# untitled.net
KiCad netlist of a schematic drawn in EAGLE
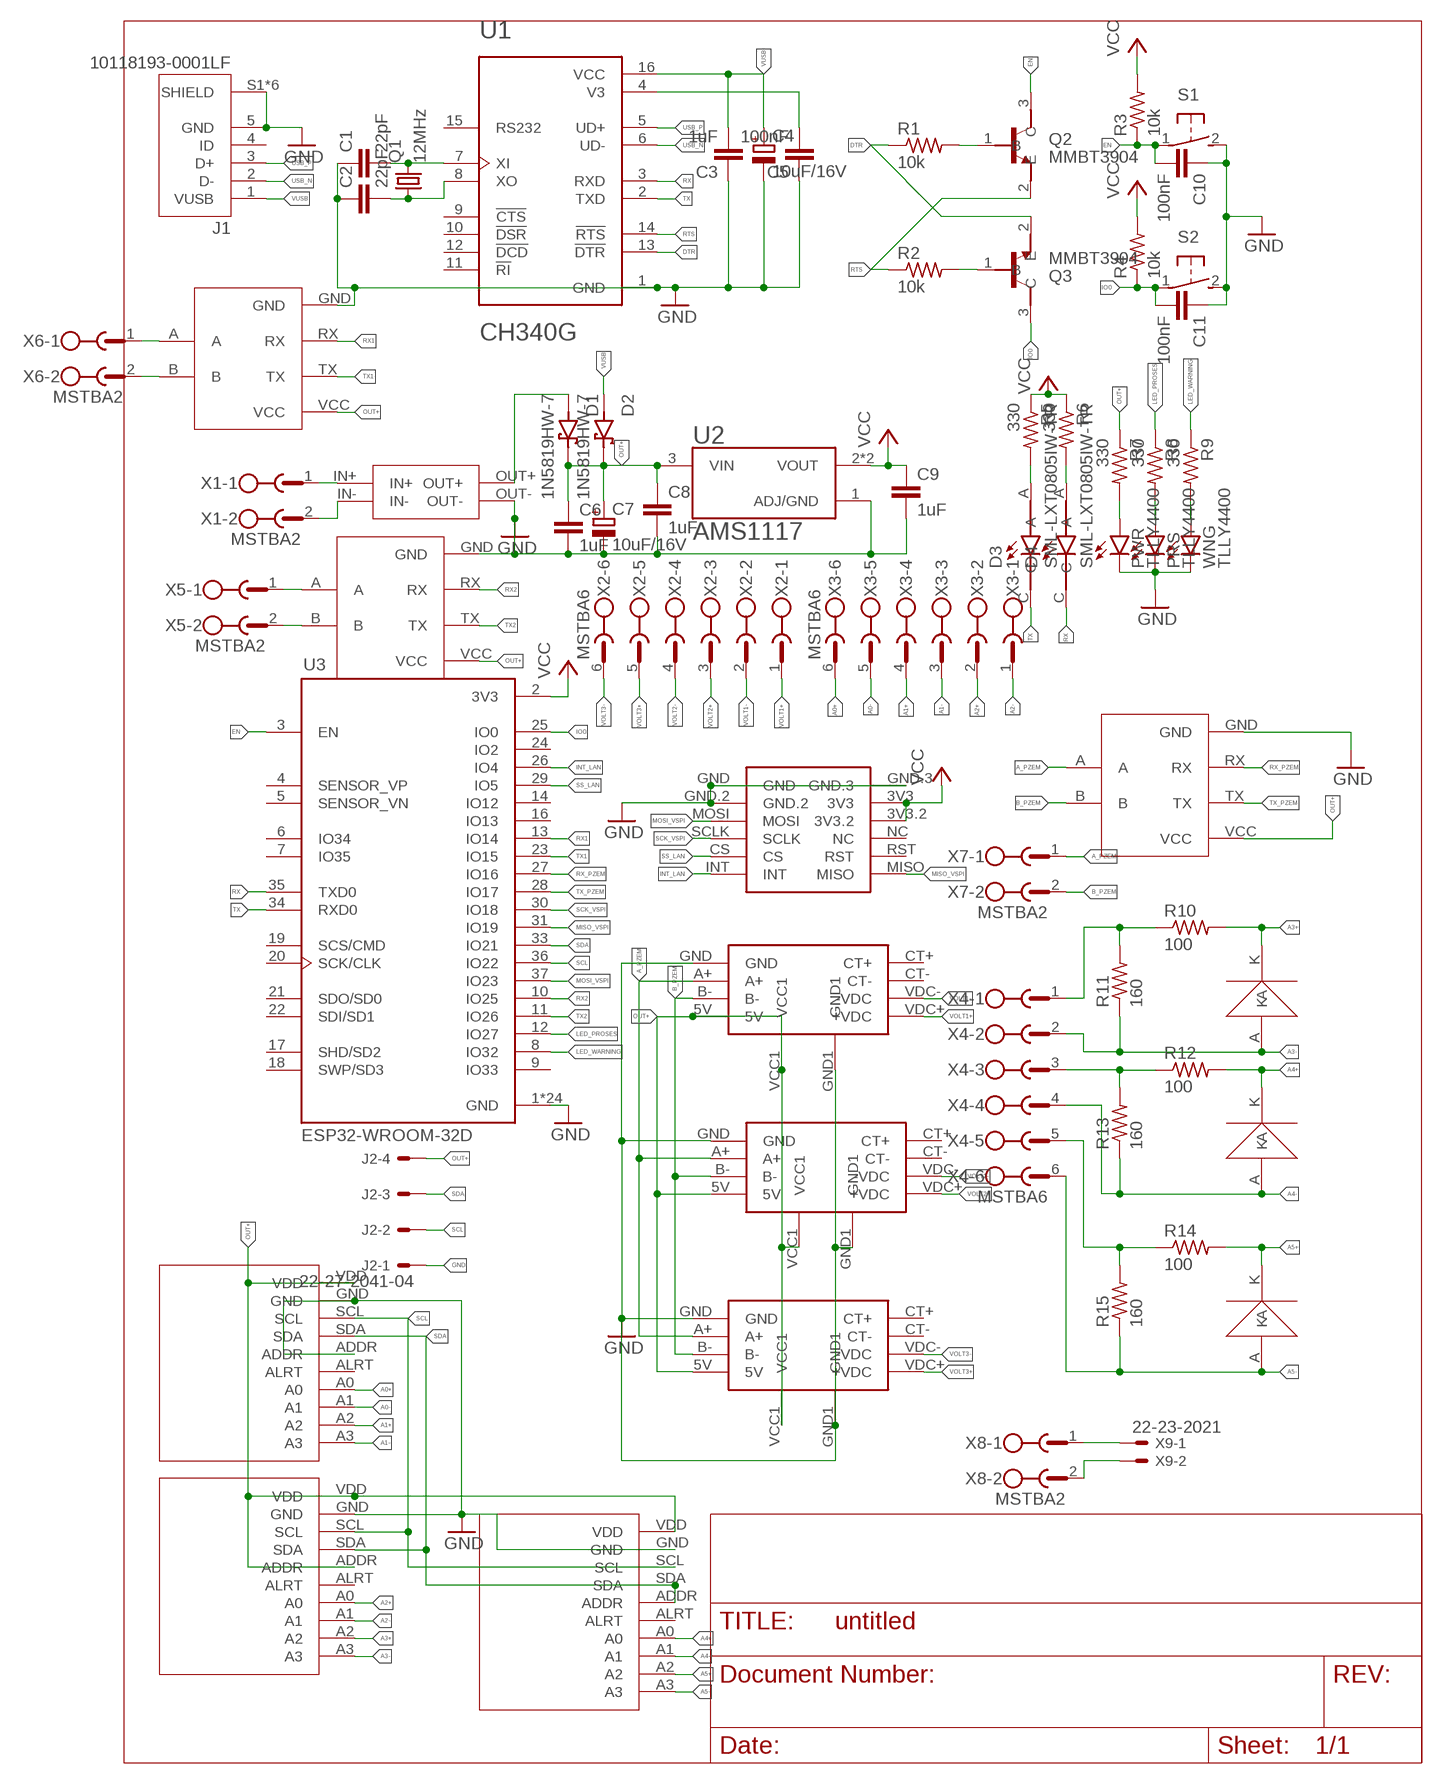
[diagram p0: schematic, sheet 1]

(export (version "E")
  (design (tool "Eeschema 10.0.6"))
  (components
    (comp (ref "ADS1")
      (value "ADS1115")
      (footprint "eagle-import:ADS1115")
      (libsource (lib "eagle-import") (part "ADS1115"))
    )
    (comp (ref "ADS2")
      (value "ADS1115")
      (footprint "eagle-import:ADS1115")
      (libsource (lib "eagle-import") (part "ADS1115"))
    )
    (comp (ref "ADS3")
      (value "ADS1115")
      (footprint "eagle-import:ADS1115")
      (libsource (lib "eagle-import") (part "ADS1115"))
    )
    (comp (ref "C1")
      (value "22pF")
      (footprint "eagle-import:C0805K")
      (libsource (lib "eagle-import") (part "C-EUC0805K"))
    )
    (comp (ref "C2")
      (value "22pF")
      (footprint "eagle-import:C0805K")
      (libsource (lib "eagle-import") (part "C-EUC0805K"))
    )
    (comp (ref "C3")
      (value "1uF")
      (footprint "eagle-import:C0805K")
      (libsource (lib "eagle-import") (part "C-EUC0805K"))
    )
    (comp (ref "C4")
      (value "10uF/16V")
      (footprint "eagle-import:153CLV-0505")
      (libsource (lib "eagle-import") (part "CPOL-EU153CLV-0505"))
    )
    (comp (ref "C5")
      (value "100nF")
      (footprint "eagle-import:C0805K")
      (libsource (lib "eagle-import") (part "C-EUC0805K"))
    )
    (comp (ref "C6")
      (value "1uF")
      (footprint "eagle-import:C0805K")
      (libsource (lib "eagle-import") (part "C-EUC0805K"))
    )
    (comp (ref "C7")
      (value "10uF/16V")
      (footprint "eagle-import:153CLV-0505")
      (libsource (lib "eagle-import") (part "CPOL-EU153CLV-0505"))
    )
    (comp (ref "C8")
      (value "1uF")
      (footprint "eagle-import:C0805K")
      (libsource (lib "eagle-import") (part "C-EUC0805K"))
    )
    (comp (ref "C9")
      (value "1uF")
      (footprint "eagle-import:C0805K")
      (libsource (lib "eagle-import") (part "C-EUC0805K"))
    )
    (comp (ref "C10")
      (value "100nF")
      (footprint "eagle-import:C0805K")
      (libsource (lib "eagle-import") (part "C-EUC0805K"))
    )
    (comp (ref "C11")
      (value "100nF")
      (footprint "eagle-import:C0805K")
      (libsource (lib "eagle-import") (part "C-EUC0805K"))
    )
    (comp (ref "D1")
      (value "1N5819HW-7")
      (footprint "eagle-import:SOD3715X145N")
      (fields (field (name "MF") "Diodes Inc."))
      (libsource (lib "eagle-import") (part "1N5819HW-7"))
    )
    (comp (ref "D2")
      (value "1N5819HW-7")
      (footprint "eagle-import:SOD3715X145N")
      (fields (field (name "MF") "Diodes Inc."))
      (libsource (lib "eagle-import") (part "1N5819HW-7"))
    )
    (comp (ref "D3")
      (value "SML-LXT0805IW-TR")
      (footprint "eagle-import:LEDC2012X120N")
      (fields (field (name "MF") "Lumex Opto/Components"))
      (libsource (lib "eagle-import") (part "SML-LXT0805IW-TR"))
    )
    (comp (ref "D4")
      (value "SML-LXT0805IW-TR")
      (footprint "eagle-import:LEDC2012X120N")
      (fields (field (name "MF") "Lumex Opto/Components"))
      (libsource (lib "eagle-import") (part "SML-LXT0805IW-TR"))
    )
    (comp (ref "J1")
      (value "10118193-0001LF")
      (footprint "eagle-import:FCI_10118193-0001LF")
      (fields (field (name "MF") "FCI"))
      (libsource (lib "eagle-import") (part "10118193-0001LF"))
    )
    (comp (ref "J2")
      (value "22-27-2041-04")
      (footprint "eagle-import:6410-04")
      (fields (field (name "MF") "MOLEX"))
      (libsource (lib "eagle-import") (part "22-?-0427-2041"))
    )
    (comp (ref "MINI1")
      (value "MINI560")
      (footprint "eagle-import:MINI560")
      (libsource (lib "eagle-import") (part "MINI560"))
    )
    (comp (ref "PRS")
      (value "TLLY4400")
      (footprint "eagle-import:LED3MM")
      (fields (field (name "MF") "VISHAY SEMICONDUCTOR"))
      (libsource (lib "eagle-import") (part "TLLY4400"))
    )
    (comp (ref "PWR")
      (value "TLLY4400")
      (footprint "eagle-import:LED3MM")
      (fields (field (name "MF") "VISHAY SEMICONDUCTOR"))
      (libsource (lib "eagle-import") (part "TLLY4400"))
    )
    (comp (ref "PZEM-DC1")
      (value "PZEM-DC")
      (footprint "eagle-import:PZEM-DC")
      (libsource (lib "eagle-import") (part "PZEM-DC"))
    )
    (comp (ref "PZEM-DC2")
      (value "PZEM-DC")
      (footprint "eagle-import:PZEM-DC")
      (libsource (lib "eagle-import") (part "PZEM-DC"))
    )
    (comp (ref "PZEM-DC3")
      (value "PZEM-DC")
      (footprint "eagle-import:PZEM-DC")
      (libsource (lib "eagle-import") (part "PZEM-DC"))
    )
    (comp (ref "Q1")
      (value "12MHz")
      (footprint "eagle-import:SM49")
      (libsource (lib "eagle-import") (part "CRYSTALSM49"))
    )
    (comp (ref "Q2")
      (value "MMBT3904")
      (footprint "eagle-import:SOT95P240X120-3N")
      (fields (field (name "MF") "ON Semiconductor"))
      (libsource (lib "eagle-import") (part "MMBT3904"))
    )
    (comp (ref "Q3")
      (value "MMBT3904")
      (footprint "eagle-import:SOT95P240X120-3N")
      (fields (field (name "MF") "ON Semiconductor"))
      (libsource (lib "eagle-import") (part "MMBT3904"))
    )
    (comp (ref "R1")
      (value "10k")
      (footprint "eagle-import:M0805")
      (libsource (lib "eagle-import") (part "R-US_M0805"))
    )
    (comp (ref "R2")
      (value "10k")
      (footprint "eagle-import:M0805")
      (libsource (lib "eagle-import") (part "R-US_M0805"))
    )
    (comp (ref "R3")
      (value "10k")
      (footprint "eagle-import:M0805")
      (libsource (lib "eagle-import") (part "R-US_M0805"))
    )
    (comp (ref "R4")
      (value "10k")
      (footprint "eagle-import:M0805")
      (libsource (lib "eagle-import") (part "R-US_M0805"))
    )
    (comp (ref "R5")
      (value "330")
      (footprint "eagle-import:M0805")
      (libsource (lib "eagle-import") (part "R-US_M0805"))
    )
    (comp (ref "R6")
      (value "330")
      (footprint "eagle-import:M0805")
      (libsource (lib "eagle-import") (part "R-US_M0805"))
    )
    (comp (ref "R7")
      (value "330")
      (footprint "eagle-import:M0805")
      (libsource (lib "eagle-import") (part "R-US_M0805"))
    )
    (comp (ref "R8")
      (value "330")
      (footprint "eagle-import:M0805")
      (libsource (lib "eagle-import") (part "R-US_M0805"))
    )
    (comp (ref "R9")
      (value "330")
      (footprint "eagle-import:M0805")
      (libsource (lib "eagle-import") (part "R-US_M0805"))
    )
    (comp (ref "R10")
      (value "100")
      (footprint "eagle-import:M0805")
      (libsource (lib "eagle-import") (part "R-US_M0805"))
    )
    (comp (ref "R11")
      (value "160")
      (footprint "eagle-import:M0805")
      (libsource (lib "eagle-import") (part "R-US_M0805"))
    )
    (comp (ref "R12")
      (value "100")
      (footprint "eagle-import:M0805")
      (libsource (lib "eagle-import") (part "R-US_M0805"))
    )
    (comp (ref "R13")
      (value "160")
      (footprint "eagle-import:M0805")
      (libsource (lib "eagle-import") (part "R-US_M0805"))
    )
    (comp (ref "R14")
      (value "100")
      (footprint "eagle-import:M0805")
      (libsource (lib "eagle-import") (part "R-US_M0805"))
    )
    (comp (ref "R15")
      (value "160")
      (footprint "eagle-import:M0805")
      (libsource (lib "eagle-import") (part "R-US_M0805"))
    )
    (comp (ref "S1")
      (value "31-XX")
      (footprint "eagle-import:B3F-31XX")
      (fields (field (name "MPN") "B3F-3100"))
      (libsource (lib "eagle-import") (part "31-XX"))
    )
    (comp (ref "S2")
      (value "31-XX")
      (footprint "eagle-import:B3F-31XX")
      (fields (field (name "MPN") "B3F-3100"))
      (libsource (lib "eagle-import") (part "31-XX"))
    )
    (comp (ref "TTL-RS1")
      (value "TTL-RS485")
      (footprint "eagle-import:TTL-RS485")
      (libsource (lib "eagle-import") (part "TTL-RS485"))
    )
    (comp (ref "TTL-RS2")
      (value "TTL-RS485")
      (footprint "eagle-import:TTL-RS485")
      (libsource (lib "eagle-import") (part "TTL-RS485"))
    )
    (comp (ref "TTL-RS3")
      (value "TTL-RS485")
      (footprint "eagle-import:TTL-RS485")
      (libsource (lib "eagle-import") (part "TTL-RS485"))
    )
    (comp (ref "U$1")
      (value "MINI_W5500")
      (footprint "eagle-import:MINI_W5500")
      (libsource (lib "eagle-import") (part "MINI_W5500"))
    )
    (comp (ref "U1")
      (value "CH340G")
      (footprint "eagle-import:SOIC127P600X180-16N")
      (fields (field (name "MF") "WCH") (field (name "MP") "Ch340G"))
      (libsource (lib "eagle-import") (part "CH340G"))
    )
    (comp (ref "U2")
      (value "AMS1117")
      (footprint "eagle-import:SOT229P700X180-4N")
      (fields (field (name "MF") "Advanced Monolithic Systems"))
      (libsource (lib "eagle-import") (part "AMS1117"))
    )
    (comp (ref "U3")
      (value "ESP32-WROOM-32D")
      (footprint "eagle-import:MODULE_ESP32-WROOM-32D")
      (fields (field (name "MF") "Espressif Systems"))
      (libsource (lib "eagle-import") (part "ESP32-WROOM-32D"))
    )
    (comp (ref "WNG")
      (value "TLLY4400")
      (footprint "eagle-import:LED3MM")
      (fields (field (name "MF") "VISHAY SEMICONDUCTOR"))
      (libsource (lib "eagle-import") (part "TLLY4400"))
    )
    (comp (ref "X1")
      (value "MSTBA2")
      (footprint "eagle-import:MSTBA2")
      (fields (field (name "MF") "FARNELL") (field (name "MPN") "1757242"))
      (libsource (lib "eagle-import") (part "MSTBA2"))
    )
    (comp (ref "X2")
      (value "MSTBA6")
      (footprint "eagle-import:MSTBA6")
      (fields (field (name "MF") "FARNELL") (field (name "MPN") "1757284"))
      (libsource (lib "eagle-import") (part "MSTBA6"))
    )
    (comp (ref "X3")
      (value "MSTBA6")
      (footprint "eagle-import:MSTBA6")
      (fields (field (name "MF") "FARNELL") (field (name "MPN") "1757284"))
      (libsource (lib "eagle-import") (part "MSTBA6"))
    )
    (comp (ref "X4")
      (value "MSTBA6")
      (footprint "eagle-import:MSTBA6")
      (fields (field (name "MF") "FARNELL") (field (name "MPN") "1757284"))
      (libsource (lib "eagle-import") (part "MSTBA6"))
    )
    (comp (ref "X5")
      (value "MSTBA2")
      (footprint "eagle-import:MSTBA2")
      (fields (field (name "MF") "FARNELL") (field (name "MPN") "1757242"))
      (libsource (lib "eagle-import") (part "MSTBA2"))
    )
    (comp (ref "X6")
      (value "MSTBA2")
      (footprint "eagle-import:MSTBA2")
      (fields (field (name "MF") "FARNELL") (field (name "MPN") "1757242"))
      (libsource (lib "eagle-import") (part "MSTBA2"))
    )
    (comp (ref "X7")
      (value "MSTBA2")
      (footprint "eagle-import:MSTBA2")
      (fields (field (name "MF") "FARNELL") (field (name "MPN") "1757242"))
      (libsource (lib "eagle-import") (part "MSTBA2"))
    )
    (comp (ref "X8")
      (value "MSTBA2")
      (footprint "eagle-import:MSTBA2")
      (fields (field (name "MF") "FARNELL") (field (name "MPN") "1757242"))
      (libsource (lib "eagle-import") (part "MSTBA2"))
    )
    (comp (ref "X9")
      (value "22-23-2021")
      (footprint "eagle-import:22-23-2021")
      (fields (field (name "MF") "MOLEX"))
      (libsource (lib "eagle-import") (part "22-23-2021"))
    )
    (comp (ref "ZENER3V1")
      (value "3v3")
      (footprint "eagle-import:DIO_LL4148")
      (libsource (lib "eagle-import") (part "ZENER3V3"))
    )
    (comp (ref "ZENER3V2")
      (value "ZENER3V3")
      (footprint "eagle-import:DIO_LL4148")
      (libsource (lib "eagle-import") (part "ZENER3V3"))
    )
    (comp (ref "ZENER3V3")
      (value "ZENER3V3")
      (footprint "eagle-import:DIO_LL4148")
      (libsource (lib "eagle-import") (part "ZENER3V3"))
    )
  )
  (nets
    (net (code "1") (name "A0+") (class "Default")
      (node (ref "ADS1") (pin "A0") (pinfunction "A0_A0") (pintype "bidirectional"))
      (node (ref "X3") (pin "6") (pinfunction "1_6") (pintype "passive"))
    )
    (net (code "2") (name "A0-") (class "Default")
      (node (ref "ADS1") (pin "A1") (pinfunction "A1_A1") (pintype "bidirectional"))
      (node (ref "X3") (pin "5") (pinfunction "1_5") (pintype "passive"))
    )
    (net (code "3") (name "A1+") (class "Default")
      (node (ref "ADS1") (pin "A2") (pinfunction "A2_A2") (pintype "bidirectional"))
      (node (ref "X3") (pin "4") (pinfunction "1_4") (pintype "passive"))
    )
    (net (code "4") (name "A1-") (class "Default")
      (node (ref "ADS1") (pin "A3") (pinfunction "A3_A3") (pintype "bidirectional"))
      (node (ref "X3") (pin "3") (pinfunction "1_3") (pintype "passive"))
    )
    (net (code "5") (name "A2+") (class "Default")
      (node (ref "ADS2") (pin "A0") (pinfunction "A0_A0") (pintype "bidirectional"))
      (node (ref "X3") (pin "2") (pinfunction "1_2") (pintype "passive"))
    )
    (net (code "6") (name "A2-") (class "Default")
      (node (ref "ADS2") (pin "A1") (pinfunction "A1_A1") (pintype "bidirectional"))
      (node (ref "X3") (pin "1") (pinfunction "1_1") (pintype "passive"))
    )
    (net (code "7") (name "A3+") (class "Default")
      (node (ref "ADS2") (pin "A2") (pinfunction "A2_A2") (pintype "bidirectional"))
      (node (ref "R10") (pin "2") (pinfunction "2_2") (pintype "passive"))
      (node (ref "ZENER3V1") (pin "K") (pinfunction "K_K") (pintype "bidirectional"))
    )
    (net (code "8") (name "A3-") (class "Default")
      (node (ref "ADS2") (pin "A3") (pinfunction "A3_A3") (pintype "bidirectional"))
      (node (ref "R11") (pin "1") (pinfunction "1_1") (pintype "passive"))
      (node (ref "X4") (pin "2") (pinfunction "1_2") (pintype "passive"))
      (node (ref "ZENER3V1") (pin "A") (pinfunction "A_A") (pintype "bidirectional"))
    )
    (net (code "9") (name "A4+") (class "Default")
      (node (ref "ADS3") (pin "A0") (pinfunction "A0_A0") (pintype "bidirectional"))
      (node (ref "R12") (pin "2") (pinfunction "2_2") (pintype "passive"))
      (node (ref "ZENER3V2") (pin "K") (pinfunction "K_K") (pintype "bidirectional"))
    )
    (net (code "10") (name "A4-") (class "Default")
      (node (ref "ADS3") (pin "A1") (pinfunction "A1_A1") (pintype "bidirectional"))
      (node (ref "R13") (pin "1") (pinfunction "1_1") (pintype "passive"))
      (node (ref "X4") (pin "4") (pinfunction "1_4") (pintype "passive"))
      (node (ref "ZENER3V2") (pin "A") (pinfunction "A_A") (pintype "bidirectional"))
    )
    (net (code "11") (name "A5+") (class "Default")
      (node (ref "ADS3") (pin "A2") (pinfunction "A2_A2") (pintype "bidirectional"))
      (node (ref "R14") (pin "2") (pinfunction "2_2") (pintype "passive"))
      (node (ref "ZENER3V3") (pin "K") (pinfunction "K_K") (pintype "bidirectional"))
    )
    (net (code "12") (name "A5-") (class "Default")
      (node (ref "ADS3") (pin "A3") (pinfunction "A3_A3") (pintype "bidirectional"))
      (node (ref "R15") (pin "1") (pinfunction "1_1") (pintype "passive"))
      (node (ref "X4") (pin "6") (pinfunction "1_6") (pintype "passive"))
      (node (ref "ZENER3V3") (pin "A") (pinfunction "A_A") (pintype "bidirectional"))
    )
    (net (code "13") (name "A_PZEM") (class "Default")
      (node (ref "PZEM-DC1") (pin "A+") (pinfunction "A+_A+") (pintype "bidirectional"))
      (node (ref "PZEM-DC2") (pin "A+") (pinfunction "A+_A+") (pintype "bidirectional"))
      (node (ref "PZEM-DC3") (pin "A+") (pinfunction "A+_A+") (pintype "bidirectional"))
      (node (ref "TTL-RS1") (pin "A") (pinfunction "A_A") (pintype "bidirectional"))
      (node (ref "X7") (pin "1") (pinfunction "1_1") (pintype "passive"))
    )
    (net (code "14") (name "B_PZEM") (class "Default")
      (node (ref "PZEM-DC1") (pin "B-") (pinfunction "B-_B-") (pintype "bidirectional"))
      (node (ref "PZEM-DC2") (pin "B-") (pinfunction "B-_B-") (pintype "bidirectional"))
      (node (ref "PZEM-DC3") (pin "B-") (pinfunction "B-_B-") (pintype "bidirectional"))
      (node (ref "TTL-RS1") (pin "B") (pinfunction "B_B") (pintype "bidirectional"))
      (node (ref "X7") (pin "2") (pinfunction "1_2") (pintype "passive"))
    )
    (net (code "15") (name "DTR") (class "Default")
      (node (ref "Q3") (pin "2") (pinfunction "E_2") (pintype "passive"))
      (node (ref "R1") (pin "1") (pinfunction "1_1") (pintype "passive"))
      (node (ref "U1") (pin "13") (pinfunction "~{DTR}_13") (pintype "output"))
    )
    (net (code "16") (name "EN") (class "Default")
      (node (ref "C10") (pin "2") (pinfunction "2_2") (pintype "passive"))
      (node (ref "Q2") (pin "3") (pinfunction "C_3") (pintype "passive"))
      (node (ref "R3") (pin "1") (pinfunction "1_1") (pintype "passive"))
      (node (ref "S1") (pin "1") (pinfunction "P_1") (pintype "passive"))
      (node (ref "U3") (pin "3") (pinfunction "EN_3") (pintype "input"))
    )
    (net (code "17") (name "GND") (class "Default")
      (node (ref "ADS1") (pin "ADDR") (pinfunction "ADDR_ADDR") (pintype "bidirectional"))
      (node (ref "ADS1") (pin "GND") (pinfunction "GND_GND") (pintype "bidirectional"))
      (node (ref "ADS2") (pin "GND") (pinfunction "GND_GND") (pintype "bidirectional"))
      (node (ref "ADS3") (pin "GND") (pinfunction "GND_GND") (pintype "bidirectional"))
      (node (ref "C1") (pin "1") (pinfunction "1_1") (pintype "passive"))
      (node (ref "C10") (pin "1") (pinfunction "1_1") (pintype "passive"))
      (node (ref "C11") (pin "1") (pinfunction "1_1") (pintype "passive"))
      (node (ref "C2") (pin "1") (pinfunction "1_1") (pintype "passive"))
      (node (ref "C3") (pin "1") (pinfunction "1_1") (pintype "passive"))
      (node (ref "C4") (pin "-") (pinfunction "-_-") (pintype "passive"))
      (node (ref "C5") (pin "1") (pinfunction "1_1") (pintype "passive"))
      (node (ref "C6") (pin "2") (pinfunction "2_2") (pintype "passive"))
      (node (ref "C7") (pin "-") (pinfunction "-_-") (pintype "passive"))
      (node (ref "C8") (pin "2") (pinfunction "2_2") (pintype "passive"))
      (node (ref "C9") (pin "2") (pinfunction "2_2") (pintype "passive"))
      (node (ref "J1") (pin "5") (pinfunction "GND_5") (pintype "passive"))
      (node (ref "J1") (pin "S1") (pinfunction "SHIELD_S1") (pintype "passive"))
      (node (ref "J1") (pin "S2") (pinfunction "SHIELD_S2") (pintype "passive"))
      (node (ref "J1") (pin "S3") (pinfunction "SHIELD_S3") (pintype "passive"))
      (node (ref "J1") (pin "S4") (pinfunction "SHIELD_S4") (pintype "passive"))
      (node (ref "J1") (pin "S5") (pinfunction "SHIELD_S5") (pintype "passive"))
      (node (ref "J1") (pin "S6") (pinfunction "SHIELD_S6") (pintype "passive"))
      (node (ref "J2") (pin "1") (pinfunction "S_1") (pintype "passive"))
      (node (ref "MINI1") (pin "OUT-") (pinfunction "OUT-_OUT-") (pintype "bidirectional"))
      (node (ref "PRS") (pin "K") (pinfunction "C_K") (pintype "passive"))
      (node (ref "PWR") (pin "K") (pinfunction "C_K") (pintype "passive"))
      (node (ref "PZEM-DC1") (pin "GND") (pinfunction "GND_GND") (pintype "bidirectional"))
      (node (ref "PZEM-DC1") (pin "GND1") (pinfunction "GND1_GND1") (pintype "bidirectional"))
      (node (ref "PZEM-DC2") (pin "GND") (pinfunction "GND_GND") (pintype "bidirectional"))
      (node (ref "PZEM-DC2") (pin "GND1") (pinfunction "GND1_GND1") (pintype "bidirectional"))
      (node (ref "PZEM-DC3") (pin "GND") (pinfunction "GND_GND") (pintype "bidirectional"))
      (node (ref "PZEM-DC3") (pin "GND1") (pinfunction "GND1_GND1") (pintype "bidirectional"))
      (node (ref "S1") (pin "2") (pinfunction "S_2") (pintype "passive"))
      (node (ref "S2") (pin "2") (pinfunction "S_2") (pintype "passive"))
      (node (ref "TTL-RS1") (pin "GND") (pinfunction "GND_GND") (pintype "bidirectional"))
      (node (ref "TTL-RS2") (pin "GND") (pinfunction "GND_GND") (pintype "bidirectional"))
      (node (ref "TTL-RS3") (pin "GND") (pinfunction "GND_GND") (pintype "bidirectional"))
      (node (ref "U$1") (pin "GND") (pinfunction "GND_GND") (pintype "bidirectional"))
      (node (ref "U$1") (pin "GND.2") (pinfunction "GND.2_GND.2") (pintype "bidirectional"))
      (node (ref "U$1") (pin "GND.3") (pinfunction "GND.3_GND.3") (pintype "bidirectional"))
      (node (ref "U1") (pin "1") (pinfunction "GND_1") (pintype "power_in"))
      (node (ref "U2") (pin "1") (pinfunction "ADJ/GND_1") (pintype "power_in"))
      (node (ref "U3") (pin "1") (pinfunction "GND_1") (pintype "power_in"))
      (node (ref "U3") (pin "15") (pinfunction "GND_15") (pintype "power_in"))
      (node (ref "U3") (pin "38") (pinfunction "GND_38") (pintype "power_in"))
      (node (ref "U3") (pin "39_1") (pinfunction "GND_39_1") (pintype "power_in"))
      (node (ref "U3") (pin "39_10") (pinfunction "GND_39_10") (pintype "power_in"))
      (node (ref "U3") (pin "39_11") (pinfunction "GND_39_11") (pintype "power_in"))
      (node (ref "U3") (pin "39_12") (pinfunction "GND_39_12") (pintype "power_in"))
      (node (ref "U3") (pin "39_13") (pinfunction "GND_39_13") (pintype "power_in"))
      (node (ref "U3") (pin "39_14") (pinfunction "GND_39_14") (pintype "power_in"))
      (node (ref "U3") (pin "39_15") (pinfunction "GND_39_15") (pintype "power_in"))
      (node (ref "U3") (pin "39_16") (pinfunction "GND_39_16") (pintype "power_in"))
      (node (ref "U3") (pin "39_17") (pinfunction "GND_39_17") (pintype "power_in"))
      (node (ref "U3") (pin "39_18") (pinfunction "GND_39_18") (pintype "power_in"))
      (node (ref "U3") (pin "39_19") (pinfunction "GND_39_19") (pintype "power_in"))
      (node (ref "U3") (pin "39_2") (pinfunction "GND_39_2") (pintype "power_in"))
      (node (ref "U3") (pin "39_20") (pinfunction "GND_39_20") (pintype "power_in"))
      (node (ref "U3") (pin "39_21") (pinfunction "GND_39_21") (pintype "power_in"))
      (node (ref "U3") (pin "39_3") (pinfunction "GND_39_3") (pintype "power_in"))
      (node (ref "U3") (pin "39_4") (pinfunction "GND_39_4") (pintype "power_in"))
      (node (ref "U3") (pin "39_5") (pinfunction "GND_39_5") (pintype "power_in"))
      (node (ref "U3") (pin "39_6") (pinfunction "GND_39_6") (pintype "power_in"))
      (node (ref "U3") (pin "39_7") (pinfunction "GND_39_7") (pintype "power_in"))
      (node (ref "U3") (pin "39_8") (pinfunction "GND_39_8") (pintype "power_in"))
      (node (ref "U3") (pin "39_9") (pinfunction "GND_39_9") (pintype "power_in"))
      (node (ref "WNG") (pin "K") (pinfunction "C_K") (pintype "passive"))
    )
    (net (code "18") (name "INT_LAN") (class "Default")
      (node (ref "U$1") (pin "INT") (pinfunction "INT_INT") (pintype "bidirectional"))
      (node (ref "U3") (pin "26") (pinfunction "IO4_26") (pintype "bidirectional"))
    )
    (net (code "19") (name "IO0") (class "Default")
      (node (ref "C11") (pin "2") (pinfunction "2_2") (pintype "passive"))
      (node (ref "Q3") (pin "3") (pinfunction "C_3") (pintype "passive"))
      (node (ref "R4") (pin "1") (pinfunction "1_1") (pintype "passive"))
      (node (ref "S2") (pin "1") (pinfunction "P_1") (pintype "passive"))
      (node (ref "U3") (pin "25") (pinfunction "IO0_25") (pintype "bidirectional"))
    )
    (net (code "20") (name "LED_PROSES") (class "Default")
      (node (ref "R8") (pin "1") (pinfunction "1_1") (pintype "passive"))
      (node (ref "U3") (pin "12") (pinfunction "IO27_12") (pintype "bidirectional"))
    )
    (net (code "21") (name "LED_WARNING") (class "Default")
      (node (ref "R9") (pin "1") (pinfunction "1_1") (pintype "passive"))
      (node (ref "U3") (pin "8") (pinfunction "IO32_8") (pintype "bidirectional"))
    )
    (net (code "22") (name "MISO_VSPI") (class "Default")
      (node (ref "U$1") (pin "MISO") (pinfunction "MISO_MISO") (pintype "bidirectional"))
      (node (ref "U3") (pin "31") (pinfunction "IO19_31") (pintype "bidirectional"))
    )
    (net (code "23") (name "MOSI_VSPI") (class "Default")
      (node (ref "U$1") (pin "MOSI") (pinfunction "MOSI_MOSI") (pintype "bidirectional"))
      (node (ref "U3") (pin "37") (pinfunction "IO23_37") (pintype "bidirectional"))
    )
    (net (code "24") (name "Net-(D1-PadA)") (class "Default")
      (node (ref "D1") (pin "A") (pinfunction "A_A") (pintype "passive"))
      (node (ref "MINI1") (pin "OUT+") (pinfunction "OUT+_OUT+") (pintype "bidirectional"))
    )
    (net (code "25") (name "Net-(D3-PadA)") (class "Default")
      (node (ref "D3") (pin "A") (pinfunction "A_A") (pintype "passive"))
      (node (ref "R5") (pin "2") (pinfunction "2_2") (pintype "passive"))
    )
    (net (code "26") (name "Net-(D4-PadA)") (class "Default")
      (node (ref "D4") (pin "A") (pinfunction "A_A") (pintype "passive"))
      (node (ref "R6") (pin "2") (pinfunction "2_2") (pintype "passive"))
    )
    (net (code "27") (name "Net-(MINI1-PadIN+)") (class "Default")
      (node (ref "MINI1") (pin "IN+") (pinfunction "IN+_IN+") (pintype "bidirectional"))
      (node (ref "X1") (pin "1") (pinfunction "1_1") (pintype "passive"))
    )
    (net (code "28") (name "Net-(PRS-PadA)") (class "Default")
      (node (ref "PRS") (pin "A") (pinfunction "A_A") (pintype "passive"))
      (node (ref "R8") (pin "2") (pinfunction "2_2") (pintype "passive"))
    )
    (net (code "29") (name "Net-(PWR-PadA)") (class "Default")
      (node (ref "PWR") (pin "A") (pinfunction "A_A") (pintype "passive"))
      (node (ref "R7") (pin "2") (pinfunction "2_2") (pintype "passive"))
    )
    (net (code "30") (name "Net-(Q2-B)") (class "Default")
      (node (ref "Q2") (pin "1") (pinfunction "B_1") (pintype "passive"))
      (node (ref "R1") (pin "2") (pinfunction "2_2") (pintype "passive"))
    )
    (net (code "31") (name "Net-(Q3-B)") (class "Default")
      (node (ref "Q3") (pin "1") (pinfunction "B_1") (pintype "passive"))
      (node (ref "R2") (pin "2") (pinfunction "2_2") (pintype "passive"))
    )
    (net (code "32") (name "Net-(R9-Pad2)") (class "Default")
      (node (ref "R9") (pin "2") (pinfunction "2_2") (pintype "passive"))
      (node (ref "WNG") (pin "A") (pinfunction "A_A") (pintype "passive"))
    )
    (net (code "33") (name "Net-(R10-Pad1)") (class "Default")
      (node (ref "R10") (pin "1") (pinfunction "1_1") (pintype "passive"))
      (node (ref "R11") (pin "2") (pinfunction "2_2") (pintype "passive"))
      (node (ref "X4") (pin "1") (pinfunction "1_1") (pintype "passive"))
    )
    (net (code "34") (name "Net-(TTL-RS2-PadA)") (class "Default")
      (node (ref "TTL-RS2") (pin "A") (pinfunction "A_A") (pintype "bidirectional"))
      (node (ref "X6") (pin "1") (pinfunction "1_1") (pintype "passive"))
    )
    (net (code "35") (name "Net-(TTL-RS3-PadA)") (class "Default")
      (node (ref "TTL-RS3") (pin "A") (pinfunction "A_A") (pintype "bidirectional"))
      (node (ref "X5") (pin "1") (pinfunction "1_1") (pintype "passive"))
    )
    (net (code "36") (name "Net-(U1-V3)") (class "Default")
      (node (ref "C5") (pin "2") (pinfunction "2_2") (pintype "passive"))
      (node (ref "U1") (pin "4") (pinfunction "V3_4") (pintype "power_in"))
    )
    (net (code "37") (name "Net-(U1-XI)") (class "Default")
      (node (ref "C1") (pin "2") (pinfunction "2_2") (pintype "passive"))
      (node (ref "Q1") (pin "2") (pinfunction "2_2") (pintype "passive"))
      (node (ref "U1") (pin "7") (pinfunction "XI_7") (pintype "input"))
    )
    (net (code "38") (name "Net-(U1-XO)") (class "Default")
      (node (ref "C2") (pin "2") (pinfunction "2_2") (pintype "passive"))
      (node (ref "Q1") (pin "1") (pinfunction "1_1") (pintype "passive"))
      (node (ref "U1") (pin "8") (pinfunction "XO_8") (pintype "output"))
    )
    (net (code "39") (name "Net-(X1B-1)") (class "Default")
      (node (ref "MINI1") (pin "IN-") (pinfunction "IN-_IN-") (pintype "bidirectional"))
      (node (ref "X1") (pin "2") (pinfunction "1_2") (pintype "passive"))
    )
    (net (code "40") (name "Net-(X4C-1)") (class "Default")
      (node (ref "R12") (pin "1") (pinfunction "1_1") (pintype "passive"))
      (node (ref "R13") (pin "2") (pinfunction "2_2") (pintype "passive"))
      (node (ref "X4") (pin "3") (pinfunction "1_3") (pintype "passive"))
    )
    (net (code "41") (name "Net-(X4E-1)") (class "Default")
      (node (ref "R14") (pin "1") (pinfunction "1_1") (pintype "passive"))
      (node (ref "R15") (pin "2") (pinfunction "2_2") (pintype "passive"))
      (node (ref "X4") (pin "5") (pinfunction "1_5") (pintype "passive"))
    )
    (net (code "42") (name "Net-(X5B-1)") (class "Default")
      (node (ref "TTL-RS3") (pin "B") (pinfunction "B_B") (pintype "bidirectional"))
      (node (ref "X5") (pin "2") (pinfunction "1_2") (pintype "passive"))
    )
    (net (code "43") (name "Net-(X6B-1)") (class "Default")
      (node (ref "TTL-RS2") (pin "B") (pinfunction "B_B") (pintype "bidirectional"))
      (node (ref "X6") (pin "2") (pinfunction "1_2") (pintype "passive"))
    )
    (net (code "44") (name "Net-(X8B-1)") (class "Default")
      (node (ref "X8") (pin "2") (pinfunction "1_2") (pintype "passive"))
      (node (ref "X9") (pin "2") (pinfunction "S_2") (pintype "passive"))
    )
    (net (code "45") (name "Net-(X9A-S)") (class "Default")
      (node (ref "X8") (pin "1") (pinfunction "1_1") (pintype "passive"))
      (node (ref "X9") (pin "1") (pinfunction "S_1") (pintype "passive"))
    )
    (net (code "46") (name "OUT+") (class "Default")
      (node (ref "ADS1") (pin "VDD") (pinfunction "VDD_VDD") (pintype "bidirectional"))
      (node (ref "ADS2") (pin "ADDR") (pinfunction "ADDR_ADDR") (pintype "bidirectional"))
      (node (ref "ADS2") (pin "VDD") (pinfunction "VDD_VDD") (pintype "bidirectional"))
      (node (ref "ADS3") (pin "VDD") (pinfunction "VDD_VDD") (pintype "bidirectional"))
      (node (ref "C6") (pin "1") (pinfunction "1_1") (pintype "passive"))
      (node (ref "C7") (pin "+") (pinfunction "+_+") (pintype "passive"))
      (node (ref "C8") (pin "1") (pinfunction "1_1") (pintype "passive"))
      (node (ref "D1") (pin "C") (pinfunction "K_C") (pintype "passive"))
      (node (ref "D2") (pin "C") (pinfunction "K_C") (pintype "passive"))
      (node (ref "J2") (pin "4") (pinfunction "S_4") (pintype "passive"))
      (node (ref "PZEM-DC1") (pin "5V") (pinfunction "5V_5V") (pintype "bidirectional"))
      (node (ref "PZEM-DC1") (pin "VCC1") (pinfunction "VCC1_VCC1") (pintype "bidirectional"))
      (node (ref "PZEM-DC2") (pin "5V") (pinfunction "5V_5V") (pintype "bidirectional"))
      (node (ref "PZEM-DC2") (pin "VCC1") (pinfunction "VCC1_VCC1") (pintype "bidirectional"))
      (node (ref "PZEM-DC3") (pin "5V") (pinfunction "5V_5V") (pintype "bidirectional"))
      (node (ref "PZEM-DC3") (pin "VCC1") (pinfunction "VCC1_VCC1") (pintype "bidirectional"))
      (node (ref "R7") (pin "1") (pinfunction "1_1") (pintype "passive"))
      (node (ref "TTL-RS1") (pin "VCC") (pinfunction "VCC_VCC") (pintype "bidirectional"))
      (node (ref "TTL-RS2") (pin "VCC") (pinfunction "VCC_VCC") (pintype "bidirectional"))
      (node (ref "TTL-RS3") (pin "VCC") (pinfunction "VCC_VCC") (pintype "bidirectional"))
      (node (ref "U2") (pin "3") (pinfunction "VIN_3") (pintype "input"))
    )
    (net (code "47") (name "RTS") (class "Default")
      (node (ref "Q2") (pin "2") (pinfunction "E_2") (pintype "passive"))
      (node (ref "R2") (pin "1") (pinfunction "1_1") (pintype "passive"))
      (node (ref "U1") (pin "14") (pinfunction "~{RTS}_14") (pintype "output"))
    )
    (net (code "48") (name "RX") (class "Default")
      (node (ref "D4") (pin "C") (pinfunction "C_C") (pintype "passive"))
      (node (ref "U1") (pin "3") (pinfunction "RXD_3") (pintype "input"))
      (node (ref "U3") (pin "35") (pinfunction "TXD0_35") (pintype "bidirectional"))
    )
    (net (code "49") (name "RX1") (class "Default")
      (node (ref "TTL-RS2") (pin "RX") (pinfunction "RX_RX") (pintype "bidirectional"))
      (node (ref "U3") (pin "13") (pinfunction "IO14_13") (pintype "bidirectional"))
    )
    (net (code "50") (name "RX2") (class "Default")
      (node (ref "TTL-RS3") (pin "RX") (pinfunction "RX_RX") (pintype "bidirectional"))
      (node (ref "U3") (pin "10") (pinfunction "IO25_10") (pintype "bidirectional"))
    )
    (net (code "51") (name "RX_PZEM") (class "Default")
      (node (ref "TTL-RS1") (pin "RX") (pinfunction "RX_RX") (pintype "bidirectional"))
      (node (ref "U3") (pin "27") (pinfunction "IO16_27") (pintype "bidirectional"))
    )
    (net (code "52") (name "SCK_VSPI") (class "Default")
      (node (ref "U$1") (pin "SCLK") (pinfunction "SCLK_SCLK") (pintype "bidirectional"))
      (node (ref "U3") (pin "30") (pinfunction "IO18_30") (pintype "bidirectional"))
    )
    (net (code "53") (name "SCL") (class "Default")
      (node (ref "ADS1") (pin "SCL") (pinfunction "SCL_SCL") (pintype "bidirectional"))
      (node (ref "ADS2") (pin "SCL") (pinfunction "SCL_SCL") (pintype "bidirectional"))
      (node (ref "ADS3") (pin "SCL") (pinfunction "SCL_SCL") (pintype "bidirectional"))
      (node (ref "J2") (pin "2") (pinfunction "S_2") (pintype "passive"))
      (node (ref "U3") (pin "36") (pinfunction "IO22_36") (pintype "bidirectional"))
    )
    (net (code "54") (name "SDA") (class "Default")
      (node (ref "ADS1") (pin "SDA") (pinfunction "SDA_SDA") (pintype "bidirectional"))
      (node (ref "ADS2") (pin "SDA") (pinfunction "SDA_SDA") (pintype "bidirectional"))
      (node (ref "ADS3") (pin "ADDR") (pinfunction "ADDR_ADDR") (pintype "bidirectional"))
      (node (ref "ADS3") (pin "SDA") (pinfunction "SDA_SDA") (pintype "bidirectional"))
      (node (ref "J2") (pin "3") (pinfunction "S_3") (pintype "passive"))
      (node (ref "U3") (pin "33") (pinfunction "IO21_33") (pintype "bidirectional"))
    )
    (net (code "55") (name "SS_LAN") (class "Default")
      (node (ref "U$1") (pin "CS") (pinfunction "CS_CS") (pintype "bidirectional"))
      (node (ref "U3") (pin "29") (pinfunction "IO5_29") (pintype "bidirectional"))
    )
    (net (code "56") (name "TX") (class "Default")
      (node (ref "D3") (pin "C") (pinfunction "C_C") (pintype "passive"))
      (node (ref "U1") (pin "2") (pinfunction "TXD_2") (pintype "output"))
      (node (ref "U3") (pin "34") (pinfunction "RXD0_34") (pintype "bidirectional"))
    )
    (net (code "57") (name "TX1") (class "Default")
      (node (ref "TTL-RS2") (pin "TX") (pinfunction "TX_TX") (pintype "bidirectional"))
      (node (ref "U3") (pin "23") (pinfunction "IO15_23") (pintype "bidirectional"))
    )
    (net (code "58") (name "TX2") (class "Default")
      (node (ref "TTL-RS3") (pin "TX") (pinfunction "TX_TX") (pintype "bidirectional"))
      (node (ref "U3") (pin "11") (pinfunction "IO26_11") (pintype "bidirectional"))
    )
    (net (code "59") (name "TX_PZEM") (class "Default")
      (node (ref "TTL-RS1") (pin "TX") (pinfunction "TX_TX") (pintype "bidirectional"))
      (node (ref "U3") (pin "28") (pinfunction "IO17_28") (pintype "bidirectional"))
    )
    (net (code "60") (name "USB_N") (class "Default")
      (node (ref "J1") (pin "2") (pinfunction "D-_2") (pintype "passive"))
      (node (ref "U1") (pin "6") (pinfunction "UD-_6") (pintype "bidirectional"))
    )
    (net (code "61") (name "USB_P") (class "Default")
      (node (ref "J1") (pin "3") (pinfunction "D+_3") (pintype "passive"))
      (node (ref "U1") (pin "5") (pinfunction "UD+_5") (pintype "bidirectional"))
    )
    (net (code "62") (name "VCC") (class "Default")
      (node (ref "C9") (pin "1") (pinfunction "1_1") (pintype "passive"))
      (node (ref "R3") (pin "2") (pinfunction "2_2") (pintype "passive"))
      (node (ref "R4") (pin "2") (pinfunction "2_2") (pintype "passive"))
      (node (ref "R5") (pin "1") (pinfunction "1_1") (pintype "passive"))
      (node (ref "R6") (pin "1") (pinfunction "1_1") (pintype "passive"))
      (node (ref "U$1") (pin "3V3") (pinfunction "3V3_3V3") (pintype "bidirectional"))
      (node (ref "U$1") (pin "3V3.2") (pinfunction "3V3.2_3V3.2") (pintype "bidirectional"))
      (node (ref "U2") (pin "2") (pinfunction "VOUT_2") (pintype "output"))
      (node (ref "U2") (pin "4") (pinfunction "VOUT_4") (pintype "output"))
      (node (ref "U3") (pin "2") (pinfunction "3V3_2") (pintype "power_in"))
    )
    (net (code "63") (name "VOLT1+") (class "Default")
      (node (ref "PZEM-DC1") (pin "VDC+") (pinfunction "+VDC_VDC+") (pintype "bidirectional"))
      (node (ref "X2") (pin "1") (pinfunction "1_1") (pintype "passive"))
    )
    (net (code "64") (name "VOLT1-") (class "Default")
      (node (ref "PZEM-DC1") (pin "VDC-") (pinfunction "-VDC_VDC-") (pintype "bidirectional"))
      (node (ref "X2") (pin "2") (pinfunction "1_2") (pintype "passive"))
    )
    (net (code "65") (name "VOLT2+") (class "Default")
      (node (ref "PZEM-DC2") (pin "VDC+") (pinfunction "+VDC_VDC+") (pintype "bidirectional"))
      (node (ref "X2") (pin "3") (pinfunction "1_3") (pintype "passive"))
    )
    (net (code "66") (name "VOLT2-") (class "Default")
      (node (ref "PZEM-DC2") (pin "VDC-") (pinfunction "-VDC_VDC-") (pintype "bidirectional"))
      (node (ref "X2") (pin "4") (pinfunction "1_4") (pintype "passive"))
    )
    (net (code "67") (name "VOLT3+") (class "Default")
      (node (ref "PZEM-DC3") (pin "VDC+") (pinfunction "+VDC_VDC+") (pintype "bidirectional"))
      (node (ref "X2") (pin "5") (pinfunction "1_5") (pintype "passive"))
    )
    (net (code "68") (name "VOLT3-") (class "Default")
      (node (ref "PZEM-DC3") (pin "VDC-") (pinfunction "-VDC_VDC-") (pintype "bidirectional"))
      (node (ref "X2") (pin "6") (pinfunction "1_6") (pintype "passive"))
    )
    (net (code "69") (name "VUSB") (class "Default")
      (node (ref "C3") (pin "2") (pinfunction "2_2") (pintype "passive"))
      (node (ref "C4") (pin "+") (pinfunction "+_+") (pintype "passive"))
      (node (ref "D2") (pin "A") (pinfunction "A_A") (pintype "passive"))
      (node (ref "J1") (pin "1") (pinfunction "VUSB_1") (pintype "passive"))
      (node (ref "U1") (pin "16") (pinfunction "VCC_16") (pintype "power_in"))
    )
    (net (code "70") (name "unconnected-(ADS1-PadALRT)") (class "Default")
      (node (ref "ADS1") (pin "ALRT") (pinfunction "ALRT_ALRT") (pintype "bidirectional"))
    )
    (net (code "71") (name "unconnected-(ADS2-PadALRT)") (class "Default")
      (node (ref "ADS2") (pin "ALRT") (pinfunction "ALRT_ALRT") (pintype "bidirectional"))
    )
    (net (code "72") (name "unconnected-(ADS3-PadALRT)") (class "Default")
      (node (ref "ADS3") (pin "ALRT") (pinfunction "ALRT_ALRT") (pintype "bidirectional"))
    )
    (net (code "73") (name "unconnected-(J1-ID-Pad4)") (class "Default")
      (node (ref "J1") (pin "4") (pinfunction "ID_4") (pintype "passive"))
    )
    (net (code "74") (name "unconnected-(PZEM-DC1-PadCT+)") (class "Default")
      (node (ref "PZEM-DC1") (pin "CT+") (pinfunction "CT+_CT+") (pintype "bidirectional"))
    )
    (net (code "75") (name "unconnected-(PZEM-DC1-PadCT-)") (class "Default")
      (node (ref "PZEM-DC1") (pin "CT-") (pinfunction "CT-_CT-") (pintype "bidirectional"))
    )
    (net (code "76") (name "unconnected-(PZEM-DC2-PadCT+)") (class "Default")
      (node (ref "PZEM-DC2") (pin "CT+") (pinfunction "CT+_CT+") (pintype "bidirectional"))
    )
    (net (code "77") (name "unconnected-(PZEM-DC2-PadCT-)") (class "Default")
      (node (ref "PZEM-DC2") (pin "CT-") (pinfunction "CT-_CT-") (pintype "bidirectional"))
    )
    (net (code "78") (name "unconnected-(PZEM-DC3-PadCT+)") (class "Default")
      (node (ref "PZEM-DC3") (pin "CT+") (pinfunction "CT+_CT+") (pintype "bidirectional"))
    )
    (net (code "79") (name "unconnected-(PZEM-DC3-PadCT-)") (class "Default")
      (node (ref "PZEM-DC3") (pin "CT-") (pinfunction "CT-_CT-") (pintype "bidirectional"))
    )
    (net (code "80") (name "unconnected-(U$1-PadNC)") (class "Default")
      (node (ref "U$1") (pin "NC") (pinfunction "NC_NC") (pintype "bidirectional"))
    )
    (net (code "81") (name "unconnected-(U$1-PadRST)") (class "Default")
      (node (ref "U$1") (pin "RST") (pinfunction "RST_RST") (pintype "bidirectional"))
    )
    (net (code "82") (name "unconnected-(U1-RS232-Pad15)") (class "Default")
      (node (ref "U1") (pin "15") (pinfunction "RS232_15") (pintype "input"))
    )
    (net (code "83") (name "unconnected-(U1-~{CTS}-Pad9)") (class "Default")
      (node (ref "U1") (pin "9") (pinfunction "~{CTS}_9") (pintype "input"))
    )
    (net (code "84") (name "unconnected-(U1-~{DCD}-Pad12)") (class "Default")
      (node (ref "U1") (pin "12") (pinfunction "~{DCD}_12") (pintype "input"))
    )
    (net (code "85") (name "unconnected-(U1-~{DSR}-Pad10)") (class "Default")
      (node (ref "U1") (pin "10") (pinfunction "~{DSR}_10") (pintype "input"))
    )
    (net (code "86") (name "unconnected-(U1-~{RI}-Pad11)") (class "Default")
      (node (ref "U1") (pin "11") (pinfunction "~{RI}_11") (pintype "input"))
    )
    (net (code "87") (name "unconnected-(U3-IO2-Pad24)") (class "Default")
      (node (ref "U3") (pin "24") (pinfunction "IO2_24") (pintype "bidirectional"))
    )
    (net (code "88") (name "unconnected-(U3-IO12-Pad14)") (class "Default")
      (node (ref "U3") (pin "14") (pinfunction "IO12_14") (pintype "bidirectional"))
    )
    (net (code "89") (name "unconnected-(U3-IO13-Pad16)") (class "Default")
      (node (ref "U3") (pin "16") (pinfunction "IO13_16") (pintype "bidirectional"))
    )
    (net (code "90") (name "unconnected-(U3-IO33-Pad9)") (class "Default")
      (node (ref "U3") (pin "9") (pinfunction "IO33_9") (pintype "bidirectional"))
    )
    (net (code "91") (name "unconnected-(U3-IO34-Pad6)") (class "Default")
      (node (ref "U3") (pin "6") (pinfunction "IO34_6") (pintype "input"))
    )
    (net (code "92") (name "unconnected-(U3-IO35-Pad7)") (class "Default")
      (node (ref "U3") (pin "7") (pinfunction "IO35_7") (pintype "input"))
    )
    (net (code "93") (name "unconnected-(U3-SCK{slash}CLK-Pad20)") (class "Default")
      (node (ref "U3") (pin "20") (pinfunction "SCK/CLK_20") (pintype "bidirectional"))
    )
    (net (code "94") (name "unconnected-(U3-SCS{slash}CMD-Pad19)") (class "Default")
      (node (ref "U3") (pin "19") (pinfunction "SCS/CMD_19") (pintype "bidirectional"))
    )
    (net (code "95") (name "unconnected-(U3-SDI{slash}SD1-Pad22)") (class "Default")
      (node (ref "U3") (pin "22") (pinfunction "SDI/SD1_22") (pintype "bidirectional"))
    )
    (net (code "96") (name "unconnected-(U3-SDO{slash}SD0-Pad21)") (class "Default")
      (node (ref "U3") (pin "21") (pinfunction "SDO/SD0_21") (pintype "bidirectional"))
    )
    (net (code "97") (name "unconnected-(U3-SENSOR_VN-Pad5)") (class "Default")
      (node (ref "U3") (pin "5") (pinfunction "SENSOR_VN_5") (pintype "input"))
    )
    (net (code "98") (name "unconnected-(U3-SENSOR_VP-Pad4)") (class "Default")
      (node (ref "U3") (pin "4") (pinfunction "SENSOR_VP_4") (pintype "input"))
    )
    (net (code "99") (name "unconnected-(U3-SHD{slash}SD2-Pad17)") (class "Default")
      (node (ref "U3") (pin "17") (pinfunction "SHD/SD2_17") (pintype "bidirectional"))
    )
    (net (code "100") (name "unconnected-(U3-SWP{slash}SD3-Pad18)") (class "Default")
      (node (ref "U3") (pin "18") (pinfunction "SWP/SD3_18") (pintype "bidirectional"))
    )
  )
)
